# SchaltplanGuideing.net
KiCad netlist of a schematic drawn in Altium Designer
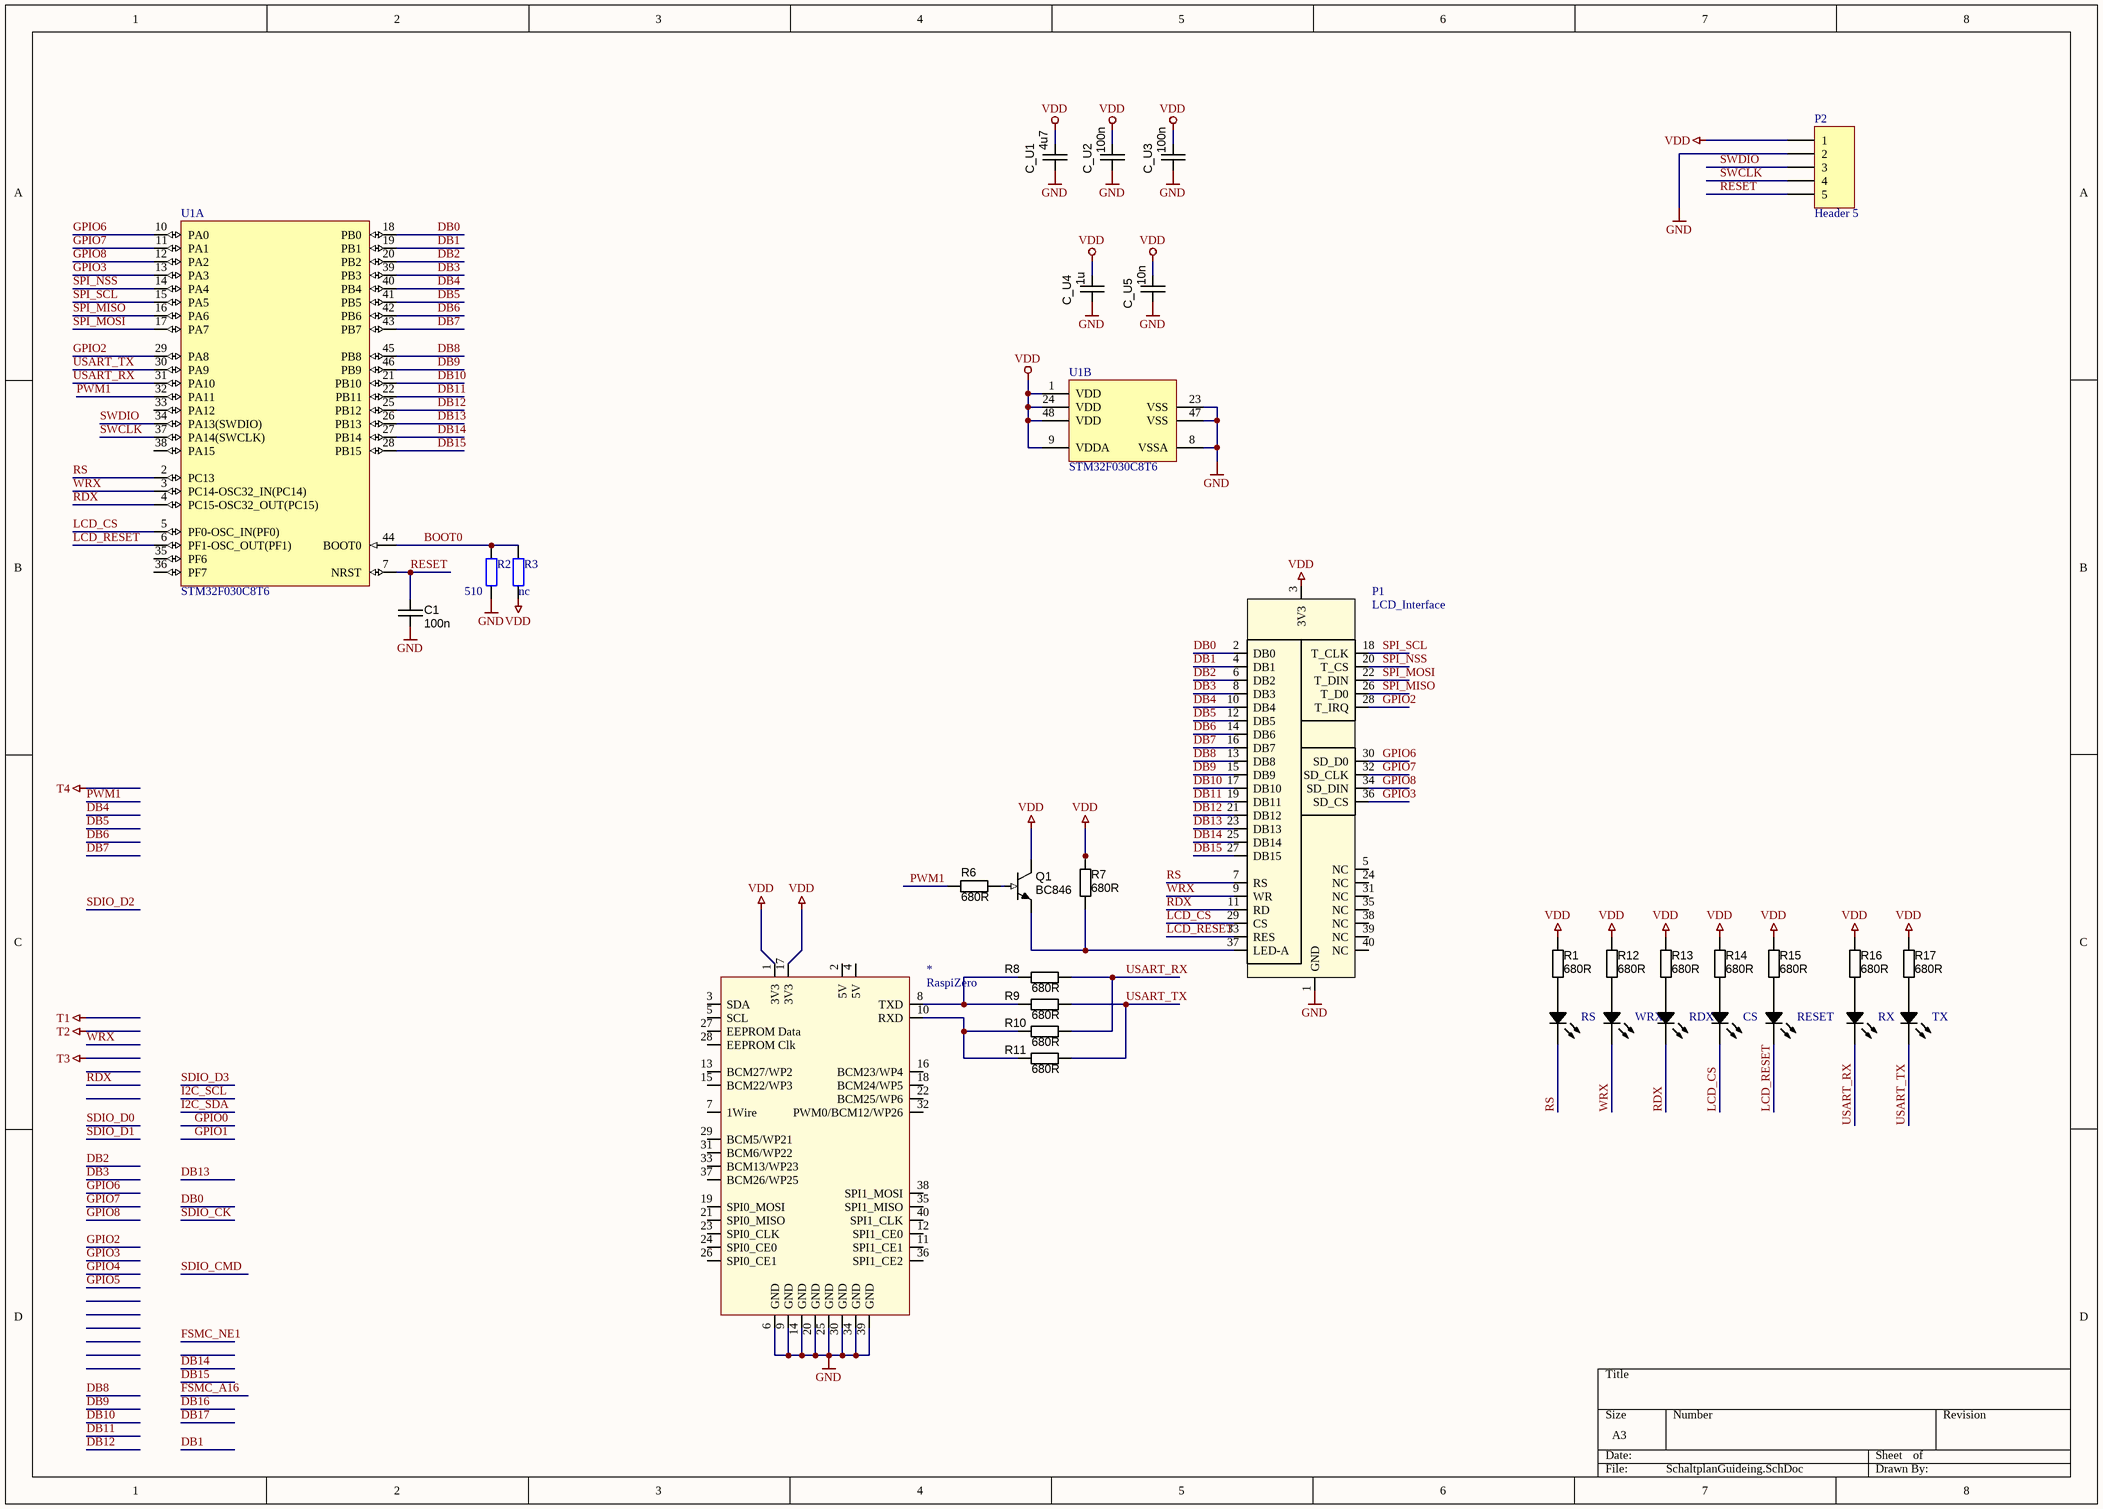
[diagram p0: SchaltplanGuideing.SchDoc]

(export (version "E")
  (design (tool "Eeschema 10.0.6"))
  (components
    (comp (ref "*") (value "RaspiZero") (footprint "PIZero") (libsource (lib "RaspiZero") (part "RaspiZero")))
    (comp (ref "C1")
      (value "100n")
      (footprint "CAPC2012N_0805")
      (description "Capacitor SMD Cer 1uF 10% 16V X7R 0603")
      (fields (field (name "TOLERANCE") "±10%") (field (name "Comment") "approved sub OK"))
      (libsource (lib "PBL - Capacitors") (part "CAPC_1u_0603_X7R_16V_10%"))
    )
    (comp (ref "CS") (value "~") (footprint "LED_0805") (libsource (lib "Standart") (part "LED_0805")))
    (comp (ref "C_U1")
      (value "4u7")
      (footprint "CAPC2012N_0805")
      (description "Capacitor SMD Cer 4,7uF 10% 16V X7R 0603")
      (fields (field (name "TOLERANCE") "±10%") (field (name "Comment") "approved sub OK"))
      (libsource (lib "PBL - Capacitors") (part "CAPC_1u_0603_X7R_16V_10%"))
    )
    (comp (ref "C_U2")
      (value "100n")
      (footprint "CAPC2012N_0805")
      (description "Capacitor SMD Cer 100nF 10% 16V X7R 0603")
      (fields (field (name "TOLERANCE") "±10%") (field (name "Comment") "approved sub OK"))
      (libsource (lib "PBL - Capacitors") (part "CAPC_1u_0603_X7R_16V_10%"))
    )
    (comp (ref "C_U3")
      (value "100n")
      (footprint "CAPC2012N_0805")
      (description "Capacitor SMD Cer 1uF 10% 16V X7R 0603")
      (fields (field (name "TOLERANCE") "±10%") (field (name "Comment") "approved sub OK"))
      (libsource (lib "PBL - Capacitors") (part "CAPC_1u_0603_X7R_16V_10%"))
    )
    (comp (ref "C_U4")
      (value "1u")
      (footprint "CAPC2012N_0805")
      (description "Capacitor SMD Cer 1uF 10% 16V X7R 0603")
      (fields (field (name "TOLERANCE") "±10%") (field (name "Comment") "approved sub OK"))
      (libsource (lib "PBL - Capacitors") (part "CAPC_1u_0603_X7R_16V_10%"))
    )
    (comp (ref "C_U5")
      (value "10n")
      (footprint "CAPC2012N_0805")
      (description "Capacitor SMD Cer 10nF 10% 16V X7R 0603")
      (fields (field (name "TOLERANCE") "±10%") (field (name "Comment") "approved sub OK"))
      (libsource (lib "PBL - Capacitors") (part "CAPC_1u_0603_X7R_16V_10%"))
    )
    (comp (ref "P1")
      (value "LCD_Interface")
      (footprint "40Pol")
      (libsource (lib "RaspiZero") (part "LCD_Interface"))
    )
    (comp (ref "P2")
      (value "Header 5")
      (footprint "HDR1X5")
      (description "Header, 5-Pin")
      (fields (field (name "PUBLISHER") "Altium Limited"))
      (libsource (lib "Miscellaneous Connectors") (part "Header 5"))
    )
    (comp (ref "Q1")
      (value "BC846")
      (footprint "SOT23-3")
      (description "Transistor SMD NPN 250mW SOT23-3")
      (libsource (lib "PBL - Transistors") (part "NPN_MMBT2222A"))
    )
    (comp (ref "R1")
      (value "680R")
      (footprint "0608_RES")
      (description "Resistor SMD chip 0.0 Ohm 0.1W 0603")
      (fields (field (name "TOLERANCE") "±5%") (field (name "Comment") "Thick Film"))
      (libsource (lib "Vectron_19550") (part "RES_0R_0603"))
    )
    (comp (ref "R2")
      (value "510")
      (footprint "RESC2012N_0805")
      (description "Resistor")
      (fields (field (name "PUBLISHER") "Altium Limited"))
      (libsource (lib "Miscellaneous Devices") (part "Res2"))
    )
    (comp (ref "R3")
      (value "nc")
      (footprint "RESC2012N_0805")
      (description "Resistor")
      (fields (field (name "PUBLISHER") "Altium Limited"))
      (libsource (lib "Miscellaneous Devices") (part "Res2"))
    )
    (comp (ref "R6")
      (value "680R")
      (footprint "0608_RES")
      (description "Resistor SMD chip 0.0 Ohm 0.1W 0603")
      (fields (field (name "TOLERANCE") "±5%") (field (name "Comment") "Thick Film"))
      (libsource (lib "") (part "RES_0R_0603_1"))
    )
    (comp (ref "R7")
      (value "680R")
      (footprint "0608_RES")
      (description "Resistor SMD chip 0.0 Ohm 0.1W 0603")
      (fields (field (name "TOLERANCE") "±5%") (field (name "Comment") "Thick Film"))
      (libsource (lib "Vectron_19550") (part "RES_0R_0603"))
    )
    (comp (ref "R8")
      (value "680R")
      (footprint "0608_RES")
      (description "Resistor SMD chip 0.0 Ohm 0.1W 0603")
      (fields (field (name "TOLERANCE") "±5%") (field (name "Comment") "Thick Film"))
      (libsource (lib "") (part "RES_0R_0603_1"))
    )
    (comp (ref "R9")
      (value "680R")
      (footprint "0608_RES")
      (description "Resistor SMD chip 0.0 Ohm 0.1W 0603")
      (fields (field (name "TOLERANCE") "±5%") (field (name "Comment") "Thick Film"))
      (libsource (lib "") (part "RES_0R_0603_1"))
    )
    (comp (ref "R10")
      (value "680R")
      (footprint "0608_RES")
      (description "Resistor SMD chip 0.0 Ohm 0.1W 0603")
      (fields (field (name "TOLERANCE") "±5%") (field (name "Comment") "Thick Film"))
      (libsource (lib "") (part "RES_0R_0603_1"))
    )
    (comp (ref "R11")
      (value "680R")
      (footprint "0608_RES")
      (description "Resistor SMD chip 0.0 Ohm 0.1W 0603")
      (fields (field (name "TOLERANCE") "±5%") (field (name "Comment") "Thick Film"))
      (libsource (lib "") (part "RES_0R_0603_1"))
    )
    (comp (ref "R12")
      (value "680R")
      (footprint "0608_RES")
      (description "Resistor SMD chip 0.0 Ohm 0.1W 0603")
      (fields (field (name "TOLERANCE") "±5%") (field (name "Comment") "Thick Film"))
      (libsource (lib "Vectron_19550") (part "RES_0R_0603"))
    )
    (comp (ref "R13")
      (value "680R")
      (footprint "0608_RES")
      (description "Resistor SMD chip 0.0 Ohm 0.1W 0603")
      (fields (field (name "TOLERANCE") "±5%") (field (name "Comment") "Thick Film"))
      (libsource (lib "Vectron_19550") (part "RES_0R_0603"))
    )
    (comp (ref "R14")
      (value "680R")
      (footprint "0608_RES")
      (description "Resistor SMD chip 0.0 Ohm 0.1W 0603")
      (fields (field (name "TOLERANCE") "±5%") (field (name "Comment") "Thick Film"))
      (libsource (lib "Vectron_19550") (part "RES_0R_0603"))
    )
    (comp (ref "R15")
      (value "680R")
      (footprint "0608_RES")
      (description "Resistor SMD chip 0.0 Ohm 0.1W 0603")
      (fields (field (name "TOLERANCE") "±5%") (field (name "Comment") "Thick Film"))
      (libsource (lib "Vectron_19550") (part "RES_0R_0603"))
    )
    (comp (ref "R16")
      (value "680R")
      (footprint "0608_RES")
      (description "Resistor SMD chip 0.0 Ohm 0.1W 0603")
      (fields (field (name "TOLERANCE") "±5%") (field (name "Comment") "Thick Film"))
      (libsource (lib "Vectron_19550") (part "RES_0R_0603"))
    )
    (comp (ref "R17")
      (value "680R")
      (footprint "0608_RES")
      (description "Resistor SMD chip 0.0 Ohm 0.1W 0603")
      (fields (field (name "TOLERANCE") "±5%") (field (name "Comment") "Thick Film"))
      (libsource (lib "Vectron_19550") (part "RES_0R_0603"))
    )
    (comp (ref "RDX") (value "~") (footprint "LED_0805") (libsource (lib "Standart") (part "LED_0805")))
    (comp (ref "RESET") (value "~") (footprint "LED_0805") (libsource (lib "Standart") (part "LED_0805")))
    (comp (ref "RS") (value "~") (footprint "LED_0805") (libsource (lib "Standart") (part "LED_0805")))
    (comp (ref "RX") (value "~") (footprint "LED_0805") (libsource (lib "Standart") (part "LED_0805")))
    (comp (ref "TX") (value "~") (footprint "LED_0805") (libsource (lib "Standart") (part "LED_0805")))
    (comp (ref "U1")
      (value "STM32F030C8T6")
      (footprint "STM-LQFP48_M")
      (libsource (lib "STMicroelectronics_STM32F030C8T6") (part "STM32F030C8T6"))
    )
    (comp (ref "WRX") (value "~") (footprint "LED_0805") (libsource (lib "Standart") (part "LED_0805")))
  )
  (nets
    (net (code "1") (name "/BOOT0") (class "Default")
      (node (ref "R2") (pin "2") (pinfunction "2_2") (pintype "passive"))
      (node (ref "R3") (pin "2") (pinfunction "2_2") (pintype "passive"))
      (node (ref "U1") (pin "44") (pinfunction "BOOT0_44") (pintype "input"))
    )
    (net (code "2") (name "/DB0") (class "Default")
      (node (ref "P1") (pin "2") (pinfunction "DB0_2") (pintype "passive"))
      (node (ref "U1") (pin "18") (pinfunction "PB0_18") (pintype "bidirectional"))
    )
    (net (code "3") (name "/DB1") (class "Default")
      (node (ref "P1") (pin "4") (pinfunction "DB1_4") (pintype "passive"))
      (node (ref "U1") (pin "19") (pinfunction "PB1_19") (pintype "bidirectional"))
    )
    (net (code "4") (name "/DB2") (class "Default")
      (node (ref "P1") (pin "6") (pinfunction "DB2_6") (pintype "passive"))
      (node (ref "U1") (pin "20") (pinfunction "PB2_20") (pintype "bidirectional"))
    )
    (net (code "5") (name "/DB3") (class "Default")
      (node (ref "P1") (pin "8") (pinfunction "DB3_8") (pintype "passive"))
      (node (ref "U1") (pin "39") (pinfunction "PB3_39") (pintype "bidirectional"))
    )
    (net (code "6") (name "/DB4") (class "Default")
      (node (ref "P1") (pin "10") (pinfunction "DB4_10") (pintype "passive"))
      (node (ref "U1") (pin "40") (pinfunction "PB4_40") (pintype "bidirectional"))
    )
    (net (code "7") (name "/DB5") (class "Default")
      (node (ref "P1") (pin "12") (pinfunction "DB5_12") (pintype "passive"))
      (node (ref "U1") (pin "41") (pinfunction "PB5_41") (pintype "bidirectional"))
    )
    (net (code "8") (name "/DB6") (class "Default")
      (node (ref "P1") (pin "14") (pinfunction "DB6_14") (pintype "passive"))
      (node (ref "U1") (pin "42") (pinfunction "PB6_42") (pintype "bidirectional"))
    )
    (net (code "9") (name "/DB7") (class "Default")
      (node (ref "P1") (pin "16") (pinfunction "DB7_16") (pintype "passive"))
      (node (ref "U1") (pin "43") (pinfunction "PB7_43") (pintype "bidirectional"))
    )
    (net (code "10") (name "/DB8") (class "Default")
      (node (ref "P1") (pin "13") (pinfunction "DB8_13") (pintype "passive"))
      (node (ref "U1") (pin "45") (pinfunction "PB8_45") (pintype "bidirectional"))
    )
    (net (code "11") (name "/DB9") (class "Default")
      (node (ref "P1") (pin "15") (pinfunction "DB9_15") (pintype "passive"))
      (node (ref "U1") (pin "46") (pinfunction "PB9_46") (pintype "bidirectional"))
    )
    (net (code "12") (name "/DB10") (class "Default")
      (node (ref "P1") (pin "17") (pinfunction "DB10_17") (pintype "passive"))
      (node (ref "U1") (pin "21") (pinfunction "PB10_21") (pintype "bidirectional"))
    )
    (net (code "13") (name "/DB11") (class "Default")
      (node (ref "P1") (pin "19") (pinfunction "DB11_19") (pintype "passive"))
      (node (ref "U1") (pin "22") (pinfunction "PB11_22") (pintype "bidirectional"))
    )
    (net (code "14") (name "/DB12") (class "Default")
      (node (ref "P1") (pin "21") (pinfunction "DB12_21") (pintype "passive"))
      (node (ref "U1") (pin "25") (pinfunction "PB12_25") (pintype "bidirectional"))
    )
    (net (code "15") (name "/DB13") (class "Default")
      (node (ref "P1") (pin "23") (pinfunction "DB13_23") (pintype "passive"))
      (node (ref "U1") (pin "26") (pinfunction "PB13_26") (pintype "bidirectional"))
    )
    (net (code "16") (name "/DB14") (class "Default")
      (node (ref "P1") (pin "25") (pinfunction "DB14_25") (pintype "passive"))
      (node (ref "U1") (pin "27") (pinfunction "PB14_27") (pintype "bidirectional"))
    )
    (net (code "17") (name "/DB15") (class "Default")
      (node (ref "P1") (pin "27") (pinfunction "DB15_27") (pintype "passive"))
      (node (ref "U1") (pin "28") (pinfunction "PB15_28") (pintype "bidirectional"))
    )
    (net (code "24") (name "/GPIO2") (class "Default")
      (node (ref "P1") (pin "28") (pinfunction "T_IRQ_28") (pintype "passive"))
      (node (ref "U1") (pin "29") (pinfunction "PA8_29") (pintype "bidirectional"))
    )
    (net (code "25") (name "/GPIO3") (class "Default")
      (node (ref "P1") (pin "36") (pinfunction "SD_CS_36") (pintype "passive"))
      (node (ref "U1") (pin "13") (pinfunction "PA3_13") (pintype "bidirectional"))
    )
    (net (code "28") (name "/GPIO6") (class "Default")
      (node (ref "P1") (pin "30") (pinfunction "SD_D0_30") (pintype "passive"))
      (node (ref "U1") (pin "10") (pinfunction "PA0_10") (pintype "bidirectional"))
    )
    (net (code "29") (name "/GPIO7") (class "Default")
      (node (ref "P1") (pin "32") (pinfunction "SD_CLK_32") (pintype "passive"))
      (node (ref "U1") (pin "11") (pinfunction "PA1_11") (pintype "bidirectional"))
    )
    (net (code "30") (name "/GPIO8") (class "Default")
      (node (ref "P1") (pin "34") (pinfunction "SD_DIN_34") (pintype "passive"))
      (node (ref "U1") (pin "12") (pinfunction "PA2_12") (pintype "bidirectional"))
    )
    (net (code "33") (name "/LCD_CS") (class "Default")
      (node (ref "CS") (pin "2") (pinfunction "2_2") (pintype "passive"))
      (node (ref "P1") (pin "29") (pinfunction "CS_29") (pintype "passive"))
      (node (ref "U1") (pin "5") (pinfunction "PF0-OSC_IN(PF0)_5") (pintype "bidirectional"))
    )
    (net (code "34") (name "/LCD_RESET") (class "Default")
      (node (ref "P1") (pin "33") (pinfunction "RES_33") (pintype "passive"))
      (node (ref "RESET") (pin "2") (pinfunction "2_2") (pintype "passive"))
      (node (ref "U1") (pin "6") (pinfunction "PF1-OSC_OUT(PF1)_6") (pintype "bidirectional"))
    )
    (net (code "35") (name "/PWM1") (class "Default")
      (node (ref "R6") (pin "2") (pinfunction "2_2") (pintype "passive"))
      (node (ref "U1") (pin "32") (pinfunction "PA11_32") (pintype "bidirectional"))
    )
    (net (code "36") (name "/RDX") (class "Default")
      (node (ref "P1") (pin "11") (pinfunction "RD_11") (pintype "passive"))
      (node (ref "RDX") (pin "2") (pinfunction "2_2") (pintype "passive"))
      (node (ref "U1") (pin "4") (pinfunction "PC15-OSC32_OUT(PC15)_4") (pintype "bidirectional"))
    )
    (net (code "37") (name "/RESET") (class "Default")
      (node (ref "C1") (pin "2") (pintype "passive"))
      (node (ref "P2") (pin "5") (pinfunction "5_5") (pintype "passive"))
      (node (ref "U1") (pin "7") (pinfunction "NRST_7") (pintype "bidirectional"))
    )
    (net (code "38") (name "/RS") (class "Default")
      (node (ref "P1") (pin "7") (pinfunction "RS_7") (pintype "passive"))
      (node (ref "RS") (pin "2") (pinfunction "2_2") (pintype "passive"))
      (node (ref "U1") (pin "2") (pinfunction "PC13_2") (pintype "bidirectional"))
    )
    (net (code "45") (name "/SPI_MISO") (class "Default")
      (node (ref "P1") (pin "26") (pinfunction "T_D0_26") (pintype "passive"))
      (node (ref "U1") (pin "16") (pinfunction "PA6_16") (pintype "bidirectional"))
    )
    (net (code "46") (name "/SPI_MOSI") (class "Default")
      (node (ref "P1") (pin "22") (pinfunction "T_DIN_22") (pintype "passive"))
      (node (ref "U1") (pin "17") (pinfunction "PA7_17") (pintype "bidirectional"))
    )
    (net (code "47") (name "/SPI_NSS") (class "Default")
      (node (ref "P1") (pin "20") (pinfunction "T_CS_20") (pintype "passive"))
      (node (ref "U1") (pin "14") (pinfunction "PA4_14") (pintype "bidirectional"))
    )
    (net (code "48") (name "/SPI_SCL") (class "Default")
      (node (ref "P1") (pin "18") (pinfunction "T_CLK_18") (pintype "passive"))
      (node (ref "U1") (pin "15") (pinfunction "PA5_15") (pintype "bidirectional"))
    )
    (net (code "49") (name "/SWCLK") (class "Default")
      (node (ref "P2") (pin "4") (pinfunction "4_4") (pintype "passive"))
      (node (ref "U1") (pin "37") (pinfunction "PA14(SWCLK)_37") (pintype "bidirectional"))
    )
    (net (code "50") (name "/SWDIO") (class "Default")
      (node (ref "P2") (pin "3") (pinfunction "3_3") (pintype "passive"))
      (node (ref "U1") (pin "34") (pinfunction "PA13(SWDIO)_34") (pintype "bidirectional"))
    )
    (net (code "51") (name "/USART_RX") (class "Default")
      (node (ref "R10") (pin "1") (pinfunction "1_1") (pintype "passive"))
      (node (ref "R8") (pin "1") (pinfunction "1_1") (pintype "passive"))
      (node (ref "RX") (pin "2") (pinfunction "2_2") (pintype "passive"))
      (node (ref "U1") (pin "31") (pinfunction "PA10_31") (pintype "bidirectional"))
    )
    (net (code "52") (name "/USART_TX") (class "Default")
      (node (ref "R11") (pin "1") (pinfunction "1_1") (pintype "passive"))
      (node (ref "R9") (pin "1") (pinfunction "1_1") (pintype "passive"))
      (node (ref "TX") (pin "2") (pinfunction "2_2") (pintype "passive"))
      (node (ref "U1") (pin "30") (pinfunction "PA9_30") (pintype "bidirectional"))
    )
    (net (code "53") (name "/WRX") (class "Default")
      (node (ref "P1") (pin "9") (pinfunction "WR_9") (pintype "passive"))
      (node (ref "U1") (pin "3") (pinfunction "PC14-OSC32_IN(PC14)_3") (pintype "bidirectional"))
      (node (ref "WRX") (pin "2") (pinfunction "2_2") (pintype "passive"))
    )
    (net (code "54") (name "GND") (class "Default")
      (node (ref "*") (pin "14") (pinfunction "GND_14") (pintype "passive"))
      (node (ref "*") (pin "20") (pinfunction "GND_20") (pintype "passive"))
      (node (ref "*") (pin "25") (pinfunction "GND_25") (pintype "passive"))
      (node (ref "*") (pin "30") (pinfunction "GND_30") (pintype "passive"))
      (node (ref "*") (pin "34") (pinfunction "GND_34") (pintype "passive"))
      (node (ref "*") (pin "39") (pinfunction "GND_39") (pintype "passive"))
      (node (ref "*") (pin "6") (pinfunction "GND_6") (pintype "passive"))
      (node (ref "*") (pin "9") (pinfunction "GND_9") (pintype "passive"))
      (node (ref "C1") (pin "1") (pintype "passive"))
      (node (ref "C_U1") (pin "2") (pintype "passive"))
      (node (ref "C_U2") (pin "2") (pintype "passive"))
      (node (ref "C_U3") (pin "2") (pintype "passive"))
      (node (ref "C_U4") (pin "2") (pintype "passive"))
      (node (ref "C_U5") (pin "2") (pintype "passive"))
      (node (ref "P1") (pin "1") (pinfunction "GND_1") (pintype "passive"))
      (node (ref "P2") (pin "2") (pinfunction "2_2") (pintype "passive"))
      (node (ref "R2") (pin "1") (pinfunction "1_1") (pintype "passive"))
      (node (ref "U1") (pin "23") (pinfunction "VSS_23") (pintype "power_in"))
      (node (ref "U1") (pin "47") (pinfunction "VSS_47") (pintype "power_in"))
      (node (ref "U1") (pin "8") (pinfunction "VSSA_8") (pintype "power_in"))
    )
    (net (code "55") (name "Net-(*-RXD)") (class "Default")
      (node (ref "*") (pin "10") (pinfunction "RXD_10") (pintype "passive"))
      (node (ref "R10") (pin "2") (pinfunction "2_2") (pintype "passive"))
      (node (ref "R11") (pin "2") (pinfunction "2_2") (pintype "passive"))
    )
    (net (code "56") (name "Net-(*-TXD)") (class "Default")
      (node (ref "*") (pin "8") (pinfunction "TXD_8") (pintype "passive"))
      (node (ref "R8") (pin "2") (pinfunction "2_2") (pintype "passive"))
      (node (ref "R9") (pin "2") (pinfunction "2_2") (pintype "passive"))
    )
    (net (code "57") (name "Net-(CS-Pad1)") (class "Default")
      (node (ref "CS") (pin "1") (pinfunction "1_1") (pintype "passive"))
      (node (ref "R14") (pin "2") (pinfunction "2_2") (pintype "passive"))
    )
    (net (code "58") (name "Net-(P1-LED-A)") (class "Default")
      (node (ref "P1") (pin "37") (pinfunction "LED-A_37") (pintype "passive"))
      (node (ref "Q1") (pin "2") (pinfunction "E_2") (pintype "passive"))
      (node (ref "R7") (pin "2") (pinfunction "2_2") (pintype "passive"))
    )
    (net (code "59") (name "Net-(Q1-B)") (class "Default")
      (node (ref "Q1") (pin "1") (pinfunction "B_1") (pintype "input"))
      (node (ref "R6") (pin "1") (pinfunction "1_1") (pintype "passive"))
    )
    (net (code "60") (name "Net-(R1-Pad2)") (class "Default")
      (node (ref "R1") (pin "2") (pinfunction "2_2") (pintype "passive"))
      (node (ref "RS") (pin "1") (pinfunction "1_1") (pintype "passive"))
    )
    (net (code "61") (name "Net-(R12-Pad2)") (class "Default")
      (node (ref "R12") (pin "2") (pinfunction "2_2") (pintype "passive"))
      (node (ref "WRX") (pin "1") (pinfunction "1_1") (pintype "passive"))
    )
    (net (code "62") (name "Net-(R13-Pad2)") (class "Default")
      (node (ref "R13") (pin "2") (pinfunction "2_2") (pintype "passive"))
      (node (ref "RDX") (pin "1") (pinfunction "1_1") (pintype "passive"))
    )
    (net (code "63") (name "Net-(R15-Pad2)") (class "Default")
      (node (ref "R15") (pin "2") (pinfunction "2_2") (pintype "passive"))
      (node (ref "RESET") (pin "1") (pinfunction "1_1") (pintype "passive"))
    )
    (net (code "64") (name "Net-(R16-Pad2)") (class "Default")
      (node (ref "R16") (pin "2") (pinfunction "2_2") (pintype "passive"))
      (node (ref "RX") (pin "1") (pinfunction "1_1") (pintype "passive"))
    )
    (net (code "65") (name "Net-(R17-Pad2)") (class "Default")
      (node (ref "R17") (pin "2") (pinfunction "2_2") (pintype "passive"))
      (node (ref "TX") (pin "1") (pinfunction "1_1") (pintype "passive"))
    )
    (net (code "70") (name "VDD") (class "Default")
      (node (ref "*") (pin "1") (pinfunction "3V3_1") (pintype "passive"))
      (node (ref "*") (pin "17") (pinfunction "3V3_17") (pintype "passive"))
      (node (ref "C_U1") (pin "1") (pintype "passive"))
      (node (ref "C_U2") (pin "1") (pintype "passive"))
      (node (ref "C_U3") (pin "1") (pintype "passive"))
      (node (ref "C_U4") (pin "1") (pintype "passive"))
      (node (ref "C_U5") (pin "1") (pintype "passive"))
      (node (ref "P1") (pin "3") (pinfunction "3V3_3") (pintype "passive"))
      (node (ref "P2") (pin "1") (pinfunction "1_1") (pintype "passive"))
      (node (ref "Q1") (pin "3") (pinfunction "C_3") (pintype "passive"))
      (node (ref "R1") (pin "1") (pinfunction "1_1") (pintype "passive"))
      (node (ref "R12") (pin "1") (pinfunction "1_1") (pintype "passive"))
      (node (ref "R13") (pin "1") (pinfunction "1_1") (pintype "passive"))
      (node (ref "R14") (pin "1") (pinfunction "1_1") (pintype "passive"))
      (node (ref "R15") (pin "1") (pinfunction "1_1") (pintype "passive"))
      (node (ref "R16") (pin "1") (pinfunction "1_1") (pintype "passive"))
      (node (ref "R17") (pin "1") (pinfunction "1_1") (pintype "passive"))
      (node (ref "R3") (pin "1") (pinfunction "1_1") (pintype "passive"))
      (node (ref "R7") (pin "1") (pinfunction "1_1") (pintype "passive"))
      (node (ref "U1") (pin "1") (pinfunction "VDD_1") (pintype "power_in"))
      (node (ref "U1") (pin "24") (pinfunction "VDD_24") (pintype "power_in"))
      (node (ref "U1") (pin "48") (pinfunction "VDD_48") (pintype "power_in"))
      (node (ref "U1") (pin "9") (pinfunction "VDDA_9") (pintype "power_in"))
    )
    (net (code "71") (name "unconnected-(*-1Wire-Pad7)") (class "Default")
      (node (ref "*") (pin "7") (pinfunction "1Wire_7") (pintype "passive"))
    )
    (net (code "72") (name "unconnected-(*-5V-Pad2)") (class "Default")
      (node (ref "*") (pin "2") (pinfunction "5V_2") (pintype "passive"))
    )
    (net (code "73") (name "unconnected-(*-5V-Pad4)") (class "Default")
      (node (ref "*") (pin "4") (pinfunction "5V_4") (pintype "passive"))
    )
    (net (code "74") (name "unconnected-(*-BCM5{slash}WP21-Pad29)") (class "Default")
      (node (ref "*") (pin "29") (pinfunction "BCM5/WP21_29") (pintype "passive"))
    )
    (net (code "75") (name "unconnected-(*-BCM6{slash}WP22-Pad31)") (class "Default")
      (node (ref "*") (pin "31") (pinfunction "BCM6/WP22_31") (pintype "passive"))
    )
    (net (code "76") (name "unconnected-(*-BCM13{slash}WP23-Pad33)") (class "Default")
      (node (ref "*") (pin "33") (pinfunction "BCM13/WP23_33") (pintype "passive"))
    )
    (net (code "77") (name "unconnected-(*-BCM22{slash}WP3-Pad15)") (class "Default")
      (node (ref "*") (pin "15") (pinfunction "BCM22/WP3_15") (pintype "passive"))
    )
    (net (code "78") (name "unconnected-(*-BCM23{slash}WP4-Pad16)") (class "Default")
      (node (ref "*") (pin "16") (pinfunction "BCM23/WP4_16") (pintype "passive"))
    )
    (net (code "79") (name "unconnected-(*-BCM24{slash}WP5-Pad18)") (class "Default")
      (node (ref "*") (pin "18") (pinfunction "BCM24/WP5_18") (pintype "passive"))
    )
    (net (code "80") (name "unconnected-(*-BCM25{slash}WP6-Pad22)") (class "Default")
      (node (ref "*") (pin "22") (pinfunction "BCM25/WP6_22") (pintype "passive"))
    )
    (net (code "81") (name "unconnected-(*-BCM26{slash}WP25-Pad37)") (class "Default")
      (node (ref "*") (pin "37") (pinfunction "BCM26/WP25_37") (pintype "passive"))
    )
    (net (code "82") (name "unconnected-(*-BCM27{slash}WP2-Pad13)") (class "Default")
      (node (ref "*") (pin "13") (pinfunction "BCM27/WP2_13") (pintype "passive"))
    )
    (net (code "83") (name "unconnected-(*-EEPROM_Clk-Pad28)") (class "Default")
      (node (ref "*") (pin "28") (pinfunction "EEPROM_Clk_28") (pintype "passive"))
    )
    (net (code "84") (name "unconnected-(*-EEPROM_Data-Pad27)") (class "Default")
      (node (ref "*") (pin "27") (pinfunction "EEPROM_Data_27") (pintype "passive"))
    )
    (net (code "85") (name "unconnected-(*-PWM0{slash}BCM12{slash}WP26-Pad32)") (class "Default")
      (node (ref "*") (pin "32") (pinfunction "PWM0/BCM12/WP26_32") (pintype "passive"))
    )
    (net (code "86") (name "unconnected-(*-SCL-Pad5)") (class "Default")
      (node (ref "*") (pin "5") (pinfunction "SCL_5") (pintype "passive"))
    )
    (net (code "87") (name "unconnected-(*-SDA-Pad3)") (class "Default")
      (node (ref "*") (pin "3") (pinfunction "SDA_3") (pintype "passive"))
    )
    (net (code "88") (name "unconnected-(*-SPI0_CE0-Pad24)") (class "Default")
      (node (ref "*") (pin "24") (pinfunction "SPI0_CE0_24") (pintype "passive"))
    )
    (net (code "89") (name "unconnected-(*-SPI0_CE1-Pad26)") (class "Default")
      (node (ref "*") (pin "26") (pinfunction "SPI0_CE1_26") (pintype "passive"))
    )
    (net (code "90") (name "unconnected-(*-SPI0_CLK-Pad23)") (class "Default")
      (node (ref "*") (pin "23") (pinfunction "SPI0_CLK_23") (pintype "passive"))
    )
    (net (code "91") (name "unconnected-(*-SPI0_MISO-Pad21)") (class "Default")
      (node (ref "*") (pin "21") (pinfunction "SPI0_MISO_21") (pintype "passive"))
    )
    (net (code "92") (name "unconnected-(*-SPI0_MOSI-Pad19)") (class "Default")
      (node (ref "*") (pin "19") (pinfunction "SPI0_MOSI_19") (pintype "passive"))
    )
    (net (code "93") (name "unconnected-(*-SPI1_CE0-Pad12)") (class "Default")
      (node (ref "*") (pin "12") (pinfunction "SPI1_CE0_12") (pintype "passive"))
    )
    (net (code "94") (name "unconnected-(*-SPI1_CE1-Pad11)") (class "Default")
      (node (ref "*") (pin "11") (pinfunction "SPI1_CE1_11") (pintype "passive"))
    )
    (net (code "95") (name "unconnected-(*-SPI1_CE2-Pad36)") (class "Default")
      (node (ref "*") (pin "36") (pinfunction "SPI1_CE2_36") (pintype "passive"))
    )
    (net (code "96") (name "unconnected-(*-SPI1_CLK-Pad40)") (class "Default")
      (node (ref "*") (pin "40") (pinfunction "SPI1_CLK_40") (pintype "passive"))
    )
    (net (code "97") (name "unconnected-(*-SPI1_MISO-Pad35)") (class "Default")
      (node (ref "*") (pin "35") (pinfunction "SPI1_MISO_35") (pintype "passive"))
    )
    (net (code "98") (name "unconnected-(*-SPI1_MOSI-Pad38)") (class "Default")
      (node (ref "*") (pin "38") (pinfunction "SPI1_MOSI_38") (pintype "passive"))
    )
    (net (code "99") (name "unconnected-(P1-NC-Pad5)") (class "Default")
      (node (ref "P1") (pin "5") (pinfunction "NC_5") (pintype "passive"))
    )
    (net (code "100") (name "unconnected-(P1-NC-Pad24)") (class "Default")
      (node (ref "P1") (pin "24") (pinfunction "NC_24") (pintype "passive"))
    )
    (net (code "101") (name "unconnected-(P1-NC-Pad31)") (class "Default")
      (node (ref "P1") (pin "31") (pinfunction "NC_31") (pintype "passive"))
    )
    (net (code "102") (name "unconnected-(P1-NC-Pad35)") (class "Default")
      (node (ref "P1") (pin "35") (pinfunction "NC_35") (pintype "passive"))
    )
    (net (code "103") (name "unconnected-(P1-NC-Pad38)") (class "Default")
      (node (ref "P1") (pin "38") (pinfunction "NC_38") (pintype "passive"))
    )
    (net (code "104") (name "unconnected-(P1-NC-Pad39)") (class "Default")
      (node (ref "P1") (pin "39") (pinfunction "NC_39") (pintype "passive"))
    )
    (net (code "105") (name "unconnected-(P1-NC-Pad40)") (class "Default")
      (node (ref "P1") (pin "40") (pinfunction "NC_40") (pintype "passive"))
    )
    (net (code "106") (name "unconnected-(U1A-PA12-Pad33)") (class "Default")
      (node (ref "U1") (pin "33") (pinfunction "PA12_33") (pintype "bidirectional"))
    )
    (net (code "107") (name "unconnected-(U1A-PA15-Pad38)") (class "Default")
      (node (ref "U1") (pin "38") (pinfunction "PA15_38") (pintype "bidirectional"))
    )
    (net (code "108") (name "unconnected-(U1A-PF6-Pad35)") (class "Default")
      (node (ref "U1") (pin "35") (pinfunction "PF6_35") (pintype "bidirectional"))
    )
    (net (code "109") (name "unconnected-(U1A-PF7-Pad36)") (class "Default")
      (node (ref "U1") (pin "36") (pinfunction "PF7_36") (pintype "bidirectional"))
    )
  )
)
